# UTMtrans.net
KiCad netlist of a schematic drawn in Altium Designer
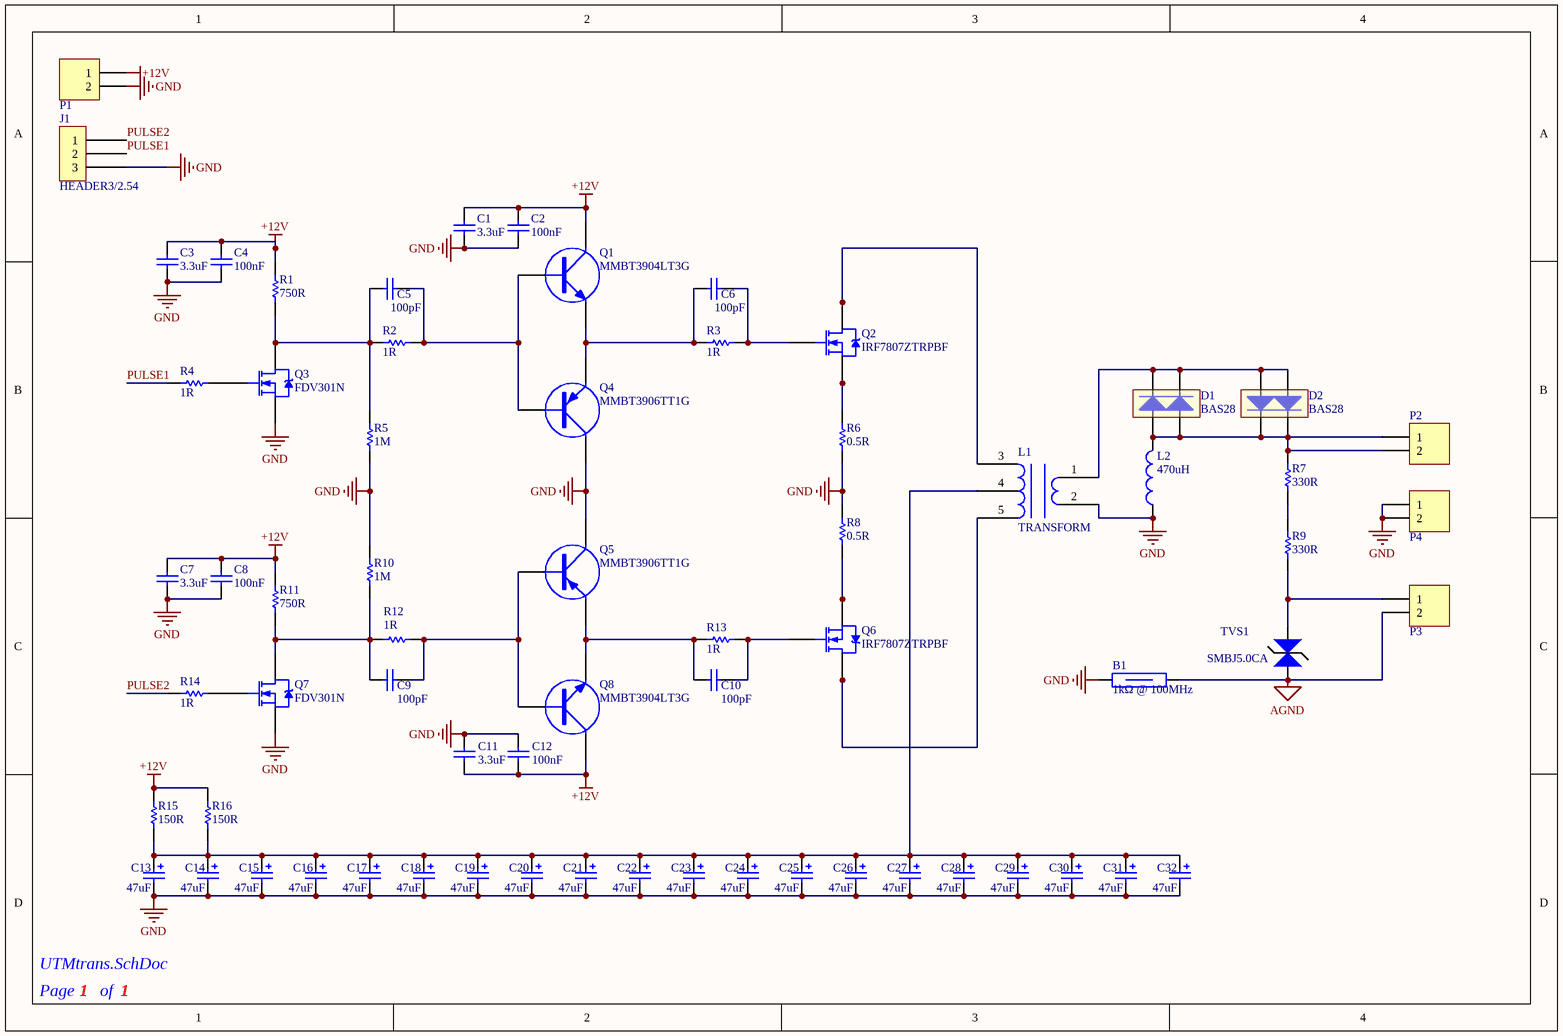
[diagram p0: UTMtrans.SchDoc]

(export (version "E")
  (design (tool "Eeschema 10.0.6"))
  (components
    (comp (ref "B1")
      (value "1kΩ @ 100MHz")
      (footprint "R1206_L")
      (description "阻抗 @ 频率 1kΩ @ 100MHz \r\n线路数 1 \r\n额定电流（最大） 2A \r\n直流电阻（DCR）（最大） 120mΩ")
      (libsource (lib "00Lib") (part "1kΩ@100MHz"))
    )
    (comp (ref "C1")
      (value "3.3uF")
      (footprint "R0805_C")
      (description "精度 ±10% \r\n容值 3.3uF \r\n额定电压 25V \r\n温漂系数（介质材料) X7R")
      (libsource (lib "00Lib") (part "3.3uF/0805/25V"))
    )
    (comp (ref "C2")
      (value "100nF")
      (footprint "R0603_C")
      (description "精度 ±10% \r\n容值 100nF \r\n额定电压 50V \r\n温漂系数（介质材料) X7R")
      (libsource (lib "00Lib") (part "100nF/0603/50V"))
    )
    (comp (ref "C3")
      (value "3.3uF")
      (footprint "R0805_C")
      (description "精度 ±10% \r\n容值 3.3uF \r\n额定电压 25V \r\n温漂系数（介质材料) X7R")
      (libsource (lib "00Lib") (part "3.3uF/0805/25V"))
    )
    (comp (ref "C4")
      (value "100nF")
      (footprint "R0603_C")
      (description "精度 ±10% \r\n容值 100nF \r\n额定电压 50V \r\n温漂系数（介质材料) X7R")
      (libsource (lib "00Lib") (part "100nF/0603/50V"))
    )
    (comp (ref "C5")
      (value "100pF")
      (footprint "R0603_C")
      (description "精度 ±5% \r\n容值 100pF \r\n额定电压 50V \r\n温漂系数（介质材料) C0G")
      (libsource (lib "00Lib") (part "100pF/0603/50V"))
    )
    (comp (ref "C6")
      (value "100pF")
      (footprint "R0603_C")
      (description "精度 ±5% \r\n容值 100pF \r\n额定电压 50V \r\n温漂系数（介质材料) C0G")
      (libsource (lib "00Lib") (part "100pF/0603/50V"))
    )
    (comp (ref "C7")
      (value "3.3uF")
      (footprint "R0805_C")
      (description "精度 ±10% \r\n容值 3.3uF \r\n额定电压 25V \r\n温漂系数（介质材料) X7R")
      (libsource (lib "00Lib") (part "3.3uF/0805/25V"))
    )
    (comp (ref "C8")
      (value "100nF")
      (footprint "R0603_C")
      (description "精度 ±10% \r\n容值 100nF \r\n额定电压 50V \r\n温漂系数（介质材料) X7R")
      (libsource (lib "00Lib") (part "100nF/0603/50V"))
    )
    (comp (ref "C9")
      (value "100pF")
      (footprint "R0603_C")
      (description "精度 ±5% \r\n容值 100pF \r\n额定电压 50V \r\n温漂系数（介质材料) C0G")
      (libsource (lib "00Lib") (part "100pF/0603/50V"))
    )
    (comp (ref "C10")
      (value "100pF")
      (footprint "R0603_C")
      (description "精度 ±5% \r\n容值 100pF \r\n额定电压 50V \r\n温漂系数（介质材料) C0G")
      (libsource (lib "00Lib") (part "100pF/0603/50V"))
    )
    (comp (ref "C11")
      (value "3.3uF")
      (footprint "R0805_C")
      (description "精度 ±10% \r\n容值 3.3uF \r\n额定电压 25V \r\n温漂系数（介质材料) X7R")
      (libsource (lib "00Lib") (part "3.3uF/0805/25V"))
    )
    (comp (ref "C12")
      (value "100nF")
      (footprint "R0603_C")
      (description "精度 ±10% \r\n容值 100nF \r\n额定电压 50V \r\n温漂系数（介质材料) X7R")
      (libsource (lib "00Lib") (part "100nF/0603/50V"))
    )
    (comp (ref "C13")
      (value "47uF")
      (footprint "CASE-E_7343")
      (description "钽电容 \r\n精度 ±10% \r\n容值 47uF \r\n额定电压 35V \r\nESR串联电阻 900 mΩ @ 100kHz \r\n工作温度 -55℃~125℃")
      (libsource (lib "00Lib") (part "Cap Pol/47uF/35V"))
    )
    (comp (ref "C14")
      (value "47uF")
      (footprint "CASE-E_7343")
      (description "钽电容 \r\n精度 ±10% \r\n容值 47uF \r\n额定电压 35V \r\nESR串联电阻 900 mΩ @ 100kHz \r\n工作温度 -55℃~125℃")
      (libsource (lib "00Lib") (part "Cap Pol/47uF/35V"))
    )
    (comp (ref "C15")
      (value "47uF")
      (footprint "CASE-E_7343")
      (description "钽电容 \r\n精度 ±10% \r\n容值 47uF \r\n额定电压 35V \r\nESR串联电阻 900 mΩ @ 100kHz \r\n工作温度 -55℃~125℃")
      (libsource (lib "00Lib") (part "Cap Pol/47uF/35V"))
    )
    (comp (ref "C16")
      (value "47uF")
      (footprint "CASE-E_7343")
      (description "钽电容 \r\n精度 ±10% \r\n容值 47uF \r\n额定电压 35V \r\nESR串联电阻 900 mΩ @ 100kHz \r\n工作温度 -55℃~125℃")
      (libsource (lib "00Lib") (part "Cap Pol/47uF/35V"))
    )
    (comp (ref "C17")
      (value "47uF")
      (footprint "CASE-E_7343")
      (description "钽电容 \r\n精度 ±10% \r\n容值 47uF \r\n额定电压 35V \r\nESR串联电阻 900 mΩ @ 100kHz \r\n工作温度 -55℃~125℃")
      (libsource (lib "00Lib") (part "Cap Pol/47uF/35V"))
    )
    (comp (ref "C18")
      (value "47uF")
      (footprint "CASE-E_7343")
      (description "钽电容 \r\n精度 ±10% \r\n容值 47uF \r\n额定电压 35V \r\nESR串联电阻 900 mΩ @ 100kHz \r\n工作温度 -55℃~125℃")
      (libsource (lib "00Lib") (part "Cap Pol/47uF/35V"))
    )
    (comp (ref "C19")
      (value "47uF")
      (footprint "CASE-E_7343")
      (description "钽电容 \r\n精度 ±10% \r\n容值 47uF \r\n额定电压 35V \r\nESR串联电阻 900 mΩ @ 100kHz \r\n工作温度 -55℃~125℃")
      (libsource (lib "00Lib") (part "Cap Pol/47uF/35V"))
    )
    (comp (ref "C20")
      (value "47uF")
      (footprint "CASE-E_7343")
      (description "钽电容 \r\n精度 ±10% \r\n容值 47uF \r\n额定电压 35V \r\nESR串联电阻 900 mΩ @ 100kHz \r\n工作温度 -55℃~125℃")
      (libsource (lib "00Lib") (part "Cap Pol/47uF/35V"))
    )
    (comp (ref "C21")
      (value "47uF")
      (footprint "CASE-E_7343")
      (description "钽电容 \r\n精度 ±10% \r\n容值 47uF \r\n额定电压 35V \r\nESR串联电阻 900 mΩ @ 100kHz \r\n工作温度 -55℃~125℃")
      (libsource (lib "00Lib") (part "Cap Pol/47uF/35V"))
    )
    (comp (ref "C22")
      (value "47uF")
      (footprint "CASE-E_7343")
      (description "钽电容 \r\n精度 ±10% \r\n容值 47uF \r\n额定电压 35V \r\nESR串联电阻 900 mΩ @ 100kHz \r\n工作温度 -55℃~125℃")
      (libsource (lib "00Lib") (part "Cap Pol/47uF/35V"))
    )
    (comp (ref "C23")
      (value "47uF")
      (footprint "CASE-E_7343")
      (description "钽电容 \r\n精度 ±10% \r\n容值 47uF \r\n额定电压 35V \r\nESR串联电阻 900 mΩ @ 100kHz \r\n工作温度 -55℃~125℃")
      (libsource (lib "00Lib") (part "Cap Pol/47uF/35V"))
    )
    (comp (ref "C24")
      (value "47uF")
      (footprint "CASE-E_7343")
      (description "钽电容 \r\n精度 ±10% \r\n容值 47uF \r\n额定电压 35V \r\nESR串联电阻 900 mΩ @ 100kHz \r\n工作温度 -55℃~125℃")
      (libsource (lib "00Lib") (part "Cap Pol/47uF/35V"))
    )
    (comp (ref "C25")
      (value "47uF")
      (footprint "CASE-E_7343")
      (description "钽电容 \r\n精度 ±10% \r\n容值 47uF \r\n额定电压 35V \r\nESR串联电阻 900 mΩ @ 100kHz \r\n工作温度 -55℃~125℃")
      (libsource (lib "00Lib") (part "Cap Pol/47uF/35V"))
    )
    (comp (ref "C26")
      (value "47uF")
      (footprint "CASE-E_7343")
      (description "钽电容 \r\n精度 ±10% \r\n容值 47uF \r\n额定电压 35V \r\nESR串联电阻 900 mΩ @ 100kHz \r\n工作温度 -55℃~125℃")
      (libsource (lib "00Lib") (part "Cap Pol/47uF/35V"))
    )
    (comp (ref "C27")
      (value "47uF")
      (footprint "CASE-E_7343")
      (description "钽电容 \r\n精度 ±10% \r\n容值 47uF \r\n额定电压 35V \r\nESR串联电阻 900 mΩ @ 100kHz \r\n工作温度 -55℃~125℃")
      (libsource (lib "00Lib") (part "Cap Pol/47uF/35V"))
    )
    (comp (ref "C28")
      (value "47uF")
      (footprint "CASE-E_7343")
      (description "钽电容 \r\n精度 ±10% \r\n容值 47uF \r\n额定电压 35V \r\nESR串联电阻 900 mΩ @ 100kHz \r\n工作温度 -55℃~125℃")
      (libsource (lib "00Lib") (part "Cap Pol/47uF/35V"))
    )
    (comp (ref "C29")
      (value "47uF")
      (footprint "CASE-E_7343")
      (description "钽电容 \r\n精度 ±10% \r\n容值 47uF \r\n额定电压 35V \r\nESR串联电阻 900 mΩ @ 100kHz \r\n工作温度 -55℃~125℃")
      (libsource (lib "00Lib") (part "Cap Pol/47uF/35V"))
    )
    (comp (ref "C30")
      (value "47uF")
      (footprint "CASE-E_7343")
      (description "钽电容 \r\n精度 ±10% \r\n容值 47uF \r\n额定电压 35V \r\nESR串联电阻 900 mΩ @ 100kHz \r\n工作温度 -55℃~125℃")
      (libsource (lib "00Lib") (part "Cap Pol/47uF/35V"))
    )
    (comp (ref "C31")
      (value "47uF")
      (footprint "CASE-E_7343")
      (description "钽电容 \r\n精度 ±10% \r\n容值 47uF \r\n额定电压 35V \r\nESR串联电阻 900 mΩ @ 100kHz \r\n工作温度 -55℃~125℃")
      (libsource (lib "00Lib") (part "Cap Pol/47uF/35V"))
    )
    (comp (ref "C32")
      (value "47uF")
      (footprint "CASE-E_7343")
      (description "钽电容 \r\n精度 ±10% \r\n容值 47uF \r\n额定电压 35V \r\nESR串联电阻 900 mΩ @ 100kHz \r\n工作温度 -55℃~125℃")
      (libsource (lib "00Lib") (part "Cap Pol/47uF/35V"))
    )
    (comp (ref "D1")
      (value "BAS28")
      (footprint "SOT143")
      (description "反向恢复时间（trr） 4ns \r\n直流反向耐压（Vr） 100V \r\n平均整流电流（Io） 150mA \r\n正向压降（Vf） 1.25V @ 150mA")
      (libsource (lib "00Lib") (part "BAS28,215"))
    )
    (comp (ref "D2")
      (value "BAS28")
      (footprint "SOT143")
      (description "反向恢复时间（trr） 4ns \r\n直流反向耐压（Vr） 100V \r\n平均整流电流（Io） 150mA \r\n正向压降（Vf） 1.25V @ 150mA")
      (libsource (lib "") (part "BAS28,215_1"))
    )
    (comp (ref "J1")
      (value "HEADER3/2.54")
      (footprint "SIP3/2.54")
      (description "3pin,单排,2.54mm间距")
      (libsource (lib "00Lib") (part "HEADER3/2.54"))
    )
    (comp (ref "L1")
      (value "TRANSFORM")
      (footprint "TRANS5")
      (description "X")
      (libsource (lib "00Lib") (part "TRANSFORM"))
    )
    (comp (ref "L2")
      (value "470uH")
      (footprint "CD0.254")
      (description "工字电感 \r\n精度 ±10% \r\n额定电流 380mA \r\n直流电阻（内阻） 1 Ohm Max \r\n电感值 470uH")
      (libsource (lib "00Lib") (part "470uH"))
    )
    (comp (ref "P1")
      (value "Header 2")
      (footprint "CP1X2")
      (description "Header, 2-Pin")
      (libsource (lib "") (part "Header 2_1"))
    )
    (comp (ref "P2")
      (value "Header 2")
      (footprint "CP1X2")
      (description "Header, 2-Pin")
      (libsource (lib "00Lib") (part "Header 2"))
    )
    (comp (ref "P3")
      (value "Header 2")
      (footprint "CP1X2")
      (description "Header, 2-Pin")
      (libsource (lib "00Lib") (part "Header 2"))
    )
    (comp (ref "P4")
      (value "Header 2")
      (footprint "CP1X2")
      (description "Header, 2-Pin")
      (libsource (lib "00Lib") (part "Header 2"))
    )
    (comp (ref "Q1")
      (value "MMBT3904LT3G")
      (footprint "SOT-23(SOT-23-3)")
      (description "300mW \r\n集电极电流Ic 200mA \r\n集射极击穿电压Vce 40V \r\n晶体管类型 NPN")
      (libsource (lib "00Lib") (part "MMBT3904LT3G"))
    )
    (comp (ref "Q2")
      (value "IRF7807ZTRPBF")
      (footprint "SOP-8_150mil")
      (libsource (lib "00Lib") (part "IRF7807ZTRPBF"))
    )
    (comp (ref "Q3") (value "FDV301N") (footprint "SOT-23") (libsource (lib "00Lib") (part "FDV301N")))
    (comp (ref "Q4")
      (value "MMBT3906TT1G")
      (footprint "SOT-23(SOT-23-3)")
      (description "额定功率 200mW \r\n集电极电流Ic 200mA \r\n集射极击穿电压Vce 40V \r\n晶体管类型 PNP")
      (libsource (lib "00Lib") (part "MMBT3906TT1G"))
    )
    (comp (ref "Q5")
      (value "MMBT3906TT1G")
      (footprint "SOT-23(SOT-23-3)")
      (description "额定功率 200mW \r\n集电极电流Ic 200mA \r\n集射极击穿电压Vce 40V \r\n晶体管类型 PNP")
      (libsource (lib "00Lib") (part "MMBT3906TT1G"))
    )
    (comp (ref "Q6")
      (value "IRF7807ZTRPBF")
      (footprint "SOP-8_150mil")
      (libsource (lib "00Lib") (part "IRF7807ZTRPBF"))
    )
    (comp (ref "Q7") (value "FDV301N") (footprint "SOT-23") (libsource (lib "00Lib") (part "FDV301N")))
    (comp (ref "Q8")
      (value "MMBT3904LT3G")
      (footprint "SOT-23(SOT-23-3)")
      (description "300mW \r\n集电极电流Ic 200mA \r\n集射极击穿电压Vce 40V \r\n晶体管类型 NPN")
      (libsource (lib "00Lib") (part "MMBT3904LT3G"))
    )
    (comp (ref "R1")
      (value "750R")
      (footprint "R2512_R")
      (description "精度 ±1% \r\n阻值 750Ω \r\n温度系数 ±100ppm/℃ \r\n功率 1W")
      (libsource (lib "00Lib") (part "750R/2512"))
    )
    (comp (ref "R2")
      (value "1R")
      (footprint "R0603_R")
      (description "±250ppm/℃ \r\n精度 ±1% \r\n阻值 1Ω \r\n功率 0.1W")
      (libsource (lib "00Lib") (part "1R/0603"))
    )
    (comp (ref "R3")
      (value "1R")
      (footprint "R0603_R")
      (description "±250ppm/℃ \r\n精度 ±1% \r\n阻值 1Ω \r\n功率 0.1W")
      (libsource (lib "00Lib") (part "1R/0603"))
    )
    (comp (ref "R4")
      (value "1R")
      (footprint "R0603_R")
      (description "±250ppm/℃ \r\n精度 ±1% \r\n阻值 1Ω \r\n功率 0.1W")
      (libsource (lib "00Lib") (part "1R/0603"))
    )
    (comp (ref "R5")
      (value "1M")
      (footprint "R0603_R")
      (description "阻值 1MΩ \r\n精度 ±1% \r\n温度系数 ±100ppm/℃ \r\n功率 0.1W")
      (libsource (lib "00Lib") (part "1M/0603"))
    )
    (comp (ref "R6")
      (value "0.5R")
      (footprint "R2512_R")
      (description "温度系数 ±800ppm/℃ \r\n功率 1W \r\n精度 ±1% \r\n阻值 0.5Ω")
      (libsource (lib "00Lib") (part "0.5R/2512"))
    )
    (comp (ref "R7")
      (value "330R")
      (footprint "R2512_R")
      (description "阻值 330Ω \r\n精度 ±1% \r\n温度系数 ±100ppm/℃ \r\n功率 1W")
      (libsource (lib "00Lib") (part "330R/2512"))
    )
    (comp (ref "R8")
      (value "0.5R")
      (footprint "R2512_R")
      (description "温度系数 ±800ppm/℃ \r\n功率 1W \r\n精度 ±1% \r\n阻值 0.5Ω")
      (libsource (lib "00Lib") (part "0.5R/2512"))
    )
    (comp (ref "R9")
      (value "330R")
      (footprint "R2512_R")
      (description "阻值 330Ω \r\n精度 ±1% \r\n温度系数 ±100ppm/℃ \r\n功率 1W")
      (libsource (lib "00Lib") (part "330R/2512"))
    )
    (comp (ref "R10")
      (value "1M")
      (footprint "R0603_R")
      (description "阻值 1MΩ \r\n精度 ±1% \r\n温度系数 ±100ppm/℃ \r\n功率 0.1W")
      (libsource (lib "00Lib") (part "1M/0603"))
    )
    (comp (ref "R11")
      (value "750R")
      (footprint "R2512_R")
      (description "精度 ±1% \r\n阻值 750Ω \r\n温度系数 ±100ppm/℃ \r\n功率 1W")
      (libsource (lib "00Lib") (part "750R/2512"))
    )
    (comp (ref "R12")
      (value "1R")
      (footprint "R0603_R")
      (description "±250ppm/℃ \r\n精度 ±1% \r\n阻值 1Ω \r\n功率 0.1W")
      (libsource (lib "00Lib") (part "1R/0603"))
    )
    (comp (ref "R13")
      (value "1R")
      (footprint "R0603_R")
      (description "±250ppm/℃ \r\n精度 ±1% \r\n阻值 1Ω \r\n功率 0.1W")
      (libsource (lib "00Lib") (part "1R/0603"))
    )
    (comp (ref "R14")
      (value "1R")
      (footprint "R0603_R")
      (description "±250ppm/℃ \r\n精度 ±1% \r\n阻值 1Ω \r\n功率 0.1W")
      (libsource (lib "00Lib") (part "1R/0603"))
    )
    (comp (ref "R15")
      (value "150R")
      (footprint "R2512_R")
      (description "功率 1W \r\n精度 ±1% \r\n温度系数 ±100ppm/℃ \r\n阻值 150Ω")
      (libsource (lib "00Lib") (part "150R/2512"))
    )
    (comp (ref "R16")
      (value "150R")
      (footprint "R2512_R")
      (description "功率 1W \r\n精度 ±1% \r\n温度系数 ±100ppm/℃ \r\n阻值 150Ω")
      (libsource (lib "00Lib") (part "150R/2512"))
    )
    (comp (ref "TVS1") (value "SMBJ5.0CA") (footprint "SMB") (libsource (lib "00Lib") (part "SMBJ5.0CA")))
  )
  (nets
    (net (code "1") (name "+12V") (class "Default")
      (node (ref "C1") (pin "2") (pinfunction "2_2") (pintype "passive"))
      (node (ref "C11") (pin "2") (pinfunction "2_2") (pintype "passive"))
      (node (ref "C12") (pin "2") (pinfunction "2_2") (pintype "passive"))
      (node (ref "C2") (pin "2") (pinfunction "2_2") (pintype "passive"))
      (node (ref "C3") (pin "2") (pinfunction "2_2") (pintype "passive"))
      (node (ref "C4") (pin "2") (pinfunction "2_2") (pintype "passive"))
      (node (ref "C7") (pin "2") (pinfunction "2_2") (pintype "passive"))
      (node (ref "C8") (pin "2") (pinfunction "2_2") (pintype "passive"))
      (node (ref "P1") (pin "1") (pinfunction "1_1") (pintype "passive"))
      (node (ref "Q1") (pin "3") (pinfunction "C_3") (pintype "passive"))
      (node (ref "Q8") (pin "3") (pinfunction "C_3") (pintype "passive"))
      (node (ref "R1") (pin "2") (pinfunction "2_2") (pintype "passive"))
      (node (ref "R11") (pin "2") (pinfunction "2_2") (pintype "passive"))
      (node (ref "R15") (pin "2") (pinfunction "2_2") (pintype "passive"))
      (node (ref "R16") (pin "2") (pinfunction "2_2") (pintype "passive"))
    )
    (net (code "2") (name "/PULSE1") (class "Default")
      (node (ref "J1") (pin "2") (pinfunction "2_2") (pintype "passive"))
      (node (ref "R4") (pin "1") (pinfunction "1_1") (pintype "passive"))
    )
    (net (code "3") (name "/PULSE2") (class "Default")
      (node (ref "J1") (pin "1") (pinfunction "1_1") (pintype "passive"))
      (node (ref "R14") (pin "1") (pinfunction "1_1") (pintype "passive"))
    )
    (net (code "4") (name "AGND") (class "Default")
      (node (ref "B1") (pin "2") (pinfunction "2_2") (pintype "passive"))
      (node (ref "P3") (pin "2") (pinfunction "2_2") (pintype "passive"))
      (node (ref "TVS1") (pin "1") (pinfunction "1_1") (pintype "passive"))
    )
    (net (code "5") (name "GND") (class "Default")
      (node (ref "B1") (pin "1") (pinfunction "1_1") (pintype "passive"))
      (node (ref "C1") (pin "1") (pinfunction "1_1") (pintype "passive"))
      (node (ref "C11") (pin "1") (pinfunction "1_1") (pintype "passive"))
      (node (ref "C12") (pin "1") (pinfunction "1_1") (pintype "passive"))
      (node (ref "C13") (pin "2") (pinfunction "2_2") (pintype "passive"))
      (node (ref "C14") (pin "2") (pinfunction "2_2") (pintype "passive"))
      (node (ref "C15") (pin "2") (pinfunction "2_2") (pintype "passive"))
      (node (ref "C16") (pin "2") (pinfunction "2_2") (pintype "passive"))
      (node (ref "C17") (pin "2") (pinfunction "2_2") (pintype "passive"))
      (node (ref "C18") (pin "2") (pinfunction "2_2") (pintype "passive"))
      (node (ref "C19") (pin "2") (pinfunction "2_2") (pintype "passive"))
      (node (ref "C2") (pin "1") (pinfunction "1_1") (pintype "passive"))
      (node (ref "C20") (pin "2") (pinfunction "2_2") (pintype "passive"))
      (node (ref "C21") (pin "2") (pinfunction "2_2") (pintype "passive"))
      (node (ref "C22") (pin "2") (pinfunction "2_2") (pintype "passive"))
      (node (ref "C23") (pin "2") (pinfunction "2_2") (pintype "passive"))
      (node (ref "C24") (pin "2") (pinfunction "2_2") (pintype "passive"))
      (node (ref "C25") (pin "2") (pinfunction "2_2") (pintype "passive"))
      (node (ref "C26") (pin "2") (pinfunction "2_2") (pintype "passive"))
      (node (ref "C27") (pin "2") (pinfunction "2_2") (pintype "passive"))
      (node (ref "C28") (pin "2") (pinfunction "2_2") (pintype "passive"))
      (node (ref "C29") (pin "2") (pinfunction "2_2") (pintype "passive"))
      (node (ref "C3") (pin "1") (pinfunction "1_1") (pintype "passive"))
      (node (ref "C30") (pin "2") (pinfunction "2_2") (pintype "passive"))
      (node (ref "C31") (pin "2") (pinfunction "2_2") (pintype "passive"))
      (node (ref "C32") (pin "2") (pinfunction "2_2") (pintype "passive"))
      (node (ref "C4") (pin "1") (pinfunction "1_1") (pintype "passive"))
      (node (ref "C7") (pin "1") (pinfunction "1_1") (pintype "passive"))
      (node (ref "C8") (pin "1") (pinfunction "1_1") (pintype "passive"))
      (node (ref "J1") (pin "3") (pinfunction "3_3") (pintype "passive"))
      (node (ref "L1") (pin "2") (pintype "passive"))
      (node (ref "L2") (pin "1") (pinfunction "1_1") (pintype "passive"))
      (node (ref "P1") (pin "2") (pinfunction "2_2") (pintype "passive"))
      (node (ref "P4") (pin "1") (pinfunction "1_1") (pintype "passive"))
      (node (ref "P4") (pin "2") (pinfunction "2_2") (pintype "passive"))
      (node (ref "Q3") (pin "2") (pinfunction "S_2") (pintype "passive"))
      (node (ref "Q4") (pin "3") (pinfunction "C_3") (pintype "passive"))
      (node (ref "Q5") (pin "3") (pinfunction "C_3") (pintype "passive"))
      (node (ref "Q7") (pin "2") (pinfunction "S_2") (pintype "passive"))
      (node (ref "R10") (pin "2") (pinfunction "2_2") (pintype "passive"))
      (node (ref "R5") (pin "1") (pinfunction "1_1") (pintype "passive"))
      (node (ref "R6") (pin "1") (pinfunction "1_1") (pintype "passive"))
      (node (ref "R8") (pin "2") (pinfunction "2_2") (pintype "passive"))
    )
    (net (code "6") (name "Net-(C13-Pad1)") (class "Default")
      (node (ref "C13") (pin "1") (pinfunction "1_1") (pintype "passive"))
      (node (ref "C14") (pin "1") (pinfunction "1_1") (pintype "passive"))
      (node (ref "C15") (pin "1") (pinfunction "1_1") (pintype "passive"))
      (node (ref "C16") (pin "1") (pinfunction "1_1") (pintype "passive"))
      (node (ref "C17") (pin "1") (pinfunction "1_1") (pintype "passive"))
      (node (ref "C18") (pin "1") (pinfunction "1_1") (pintype "passive"))
      (node (ref "C19") (pin "1") (pinfunction "1_1") (pintype "passive"))
      (node (ref "C20") (pin "1") (pinfunction "1_1") (pintype "passive"))
      (node (ref "C21") (pin "1") (pinfunction "1_1") (pintype "passive"))
      (node (ref "C22") (pin "1") (pinfunction "1_1") (pintype "passive"))
      (node (ref "C23") (pin "1") (pinfunction "1_1") (pintype "passive"))
      (node (ref "C24") (pin "1") (pinfunction "1_1") (pintype "passive"))
      (node (ref "C25") (pin "1") (pinfunction "1_1") (pintype "passive"))
      (node (ref "C26") (pin "1") (pinfunction "1_1") (pintype "passive"))
      (node (ref "C27") (pin "1") (pinfunction "1_1") (pintype "passive"))
      (node (ref "C28") (pin "1") (pinfunction "1_1") (pintype "passive"))
      (node (ref "C29") (pin "1") (pinfunction "1_1") (pintype "passive"))
      (node (ref "C30") (pin "1") (pinfunction "1_1") (pintype "passive"))
      (node (ref "C31") (pin "1") (pinfunction "1_1") (pintype "passive"))
      (node (ref "C32") (pin "1") (pinfunction "1_1") (pintype "passive"))
      (node (ref "L1") (pin "4") (pintype "passive"))
      (node (ref "R15") (pin "1") (pinfunction "1_1") (pintype "passive"))
      (node (ref "R16") (pin "1") (pinfunction "1_1") (pintype "passive"))
    )
    (net (code "7") (name "Net-(D1-A-Pad3)") (class "Default")
      (node (ref "D1") (pin "3") (pinfunction "A_3") (pintype "passive"))
      (node (ref "D1") (pin "4") (pinfunction "A_4") (pintype "passive"))
      (node (ref "D2") (pin "1") (pinfunction "K_1") (pintype "passive"))
      (node (ref "D2") (pin "2") (pinfunction "K_2") (pintype "passive"))
      (node (ref "L2") (pin "2") (pinfunction "2_2") (pintype "passive"))
      (node (ref "P2") (pin "1") (pinfunction "1_1") (pintype "passive"))
      (node (ref "P2") (pin "2") (pinfunction "2_2") (pintype "passive"))
      (node (ref "R7") (pin "2") (pinfunction "2_2") (pintype "passive"))
    )
    (net (code "8") (name "Net-(D1-K-Pad1)") (class "Default")
      (node (ref "D1") (pin "1") (pinfunction "K_1") (pintype "passive"))
      (node (ref "D1") (pin "2") (pinfunction "K_2") (pintype "passive"))
      (node (ref "D2") (pin "3") (pinfunction "A_3") (pintype "passive"))
      (node (ref "D2") (pin "4") (pinfunction "A_4") (pintype "passive"))
      (node (ref "L1") (pin "1") (pintype "passive"))
    )
    (net (code "9") (name "Net-(L1-Pad3)") (class "Default")
      (node (ref "L1") (pin "3") (pintype "passive"))
      (node (ref "Q2") (pin "5") (pinfunction "D_5") (pintype "passive"))
      (node (ref "Q2") (pin "6") (pinfunction "D_6") (pintype "passive"))
      (node (ref "Q2") (pin "7") (pinfunction "D_7") (pintype "passive"))
      (node (ref "Q2") (pin "8") (pinfunction "D_8") (pintype "passive"))
    )
    (net (code "10") (name "Net-(L1-Pad5)") (class "Default")
      (node (ref "L1") (pin "5") (pintype "passive"))
      (node (ref "Q6") (pin "5") (pinfunction "D_5") (pintype "passive"))
      (node (ref "Q6") (pin "6") (pinfunction "D_6") (pintype "passive"))
      (node (ref "Q6") (pin "7") (pinfunction "D_7") (pintype "passive"))
      (node (ref "Q6") (pin "8") (pinfunction "D_8") (pintype "passive"))
    )
    (net (code "11") (name "Net-(P3-Pad1)") (class "Default")
      (node (ref "P3") (pin "1") (pinfunction "1_1") (pintype "passive"))
      (node (ref "R9") (pin "1") (pinfunction "1_1") (pintype "passive"))
      (node (ref "TVS1") (pin "2") (pinfunction "2_2") (pintype "passive"))
    )
    (net (code "12") (name "Net-(Q1-B)") (class "Default")
      (node (ref "C5") (pin "1") (pinfunction "1_1") (pintype "passive"))
      (node (ref "Q1") (pin "1") (pinfunction "B_1") (pintype "passive"))
      (node (ref "Q4") (pin "1") (pinfunction "B_1") (pintype "passive"))
      (node (ref "R2") (pin "1") (pinfunction "1_1") (pintype "passive"))
    )
    (net (code "13") (name "Net-(Q1-E)") (class "Default")
      (node (ref "C6") (pin "1") (pinfunction "1_1") (pintype "passive"))
      (node (ref "Q1") (pin "2") (pinfunction "E_2") (pintype "passive"))
      (node (ref "Q4") (pin "2") (pinfunction "E_2") (pintype "passive"))
      (node (ref "R3") (pin "1") (pinfunction "1_1") (pintype "passive"))
    )
    (net (code "14") (name "Net-(Q2-G)") (class "Default")
      (node (ref "C6") (pin "2") (pinfunction "2_2") (pintype "passive"))
      (node (ref "Q2") (pin "4") (pinfunction "G_4") (pintype "passive"))
      (node (ref "R3") (pin "2") (pinfunction "2_2") (pintype "passive"))
    )
    (net (code "15") (name "Net-(Q2-S-Pad1)") (class "Default")
      (node (ref "Q2") (pin "1") (pinfunction "S_1") (pintype "passive"))
      (node (ref "Q2") (pin "2") (pinfunction "S_2") (pintype "passive"))
      (node (ref "Q2") (pin "3") (pinfunction "S_3") (pintype "passive"))
      (node (ref "R6") (pin "2") (pinfunction "2_2") (pintype "passive"))
    )
    (net (code "16") (name "Net-(Q3-D)") (class "Default")
      (node (ref "C5") (pin "2") (pinfunction "2_2") (pintype "passive"))
      (node (ref "Q3") (pin "3") (pinfunction "D_3") (pintype "passive"))
      (node (ref "R1") (pin "1") (pinfunction "1_1") (pintype "passive"))
      (node (ref "R2") (pin "2") (pinfunction "2_2") (pintype "passive"))
      (node (ref "R5") (pin "2") (pinfunction "2_2") (pintype "passive"))
    )
    (net (code "17") (name "Net-(Q3-G)") (class "Default")
      (node (ref "Q3") (pin "1") (pinfunction "G_1") (pintype "passive"))
      (node (ref "R4") (pin "2") (pinfunction "2_2") (pintype "passive"))
    )
    (net (code "18") (name "Net-(Q5-B)") (class "Default")
      (node (ref "C9") (pin "2") (pinfunction "2_2") (pintype "passive"))
      (node (ref "Q5") (pin "1") (pinfunction "B_1") (pintype "passive"))
      (node (ref "Q8") (pin "1") (pinfunction "B_1") (pintype "passive"))
      (node (ref "R12") (pin "2") (pinfunction "2_2") (pintype "passive"))
    )
    (net (code "19") (name "Net-(Q5-E)") (class "Default")
      (node (ref "C10") (pin "1") (pinfunction "1_1") (pintype "passive"))
      (node (ref "Q5") (pin "2") (pinfunction "E_2") (pintype "passive"))
      (node (ref "Q8") (pin "2") (pinfunction "E_2") (pintype "passive"))
      (node (ref "R13") (pin "1") (pinfunction "1_1") (pintype "passive"))
    )
    (net (code "20") (name "Net-(Q6-G)") (class "Default")
      (node (ref "C10") (pin "2") (pinfunction "2_2") (pintype "passive"))
      (node (ref "Q6") (pin "4") (pinfunction "G_4") (pintype "passive"))
      (node (ref "R13") (pin "2") (pinfunction "2_2") (pintype "passive"))
    )
    (net (code "21") (name "Net-(Q6-S-Pad1)") (class "Default")
      (node (ref "Q6") (pin "1") (pinfunction "S_1") (pintype "passive"))
      (node (ref "Q6") (pin "2") (pinfunction "S_2") (pintype "passive"))
      (node (ref "Q6") (pin "3") (pinfunction "S_3") (pintype "passive"))
      (node (ref "R8") (pin "1") (pinfunction "1_1") (pintype "passive"))
    )
    (net (code "22") (name "Net-(Q7-D)") (class "Default")
      (node (ref "C9") (pin "1") (pinfunction "1_1") (pintype "passive"))
      (node (ref "Q7") (pin "3") (pinfunction "D_3") (pintype "passive"))
      (node (ref "R10") (pin "1") (pinfunction "1_1") (pintype "passive"))
      (node (ref "R11") (pin "1") (pinfunction "1_1") (pintype "passive"))
      (node (ref "R12") (pin "1") (pinfunction "1_1") (pintype "passive"))
    )
    (net (code "23") (name "Net-(Q7-G)") (class "Default")
      (node (ref "Q7") (pin "1") (pinfunction "G_1") (pintype "passive"))
      (node (ref "R14") (pin "2") (pinfunction "2_2") (pintype "passive"))
    )
    (net (code "24") (name "Net-(R7-Pad1)") (class "Default")
      (node (ref "R7") (pin "1") (pinfunction "1_1") (pintype "passive"))
      (node (ref "R9") (pin "2") (pinfunction "2_2") (pintype "passive"))
    )
  )
)
